# MCU.net
KiCad netlist of a schematic drawn in Altium Designer
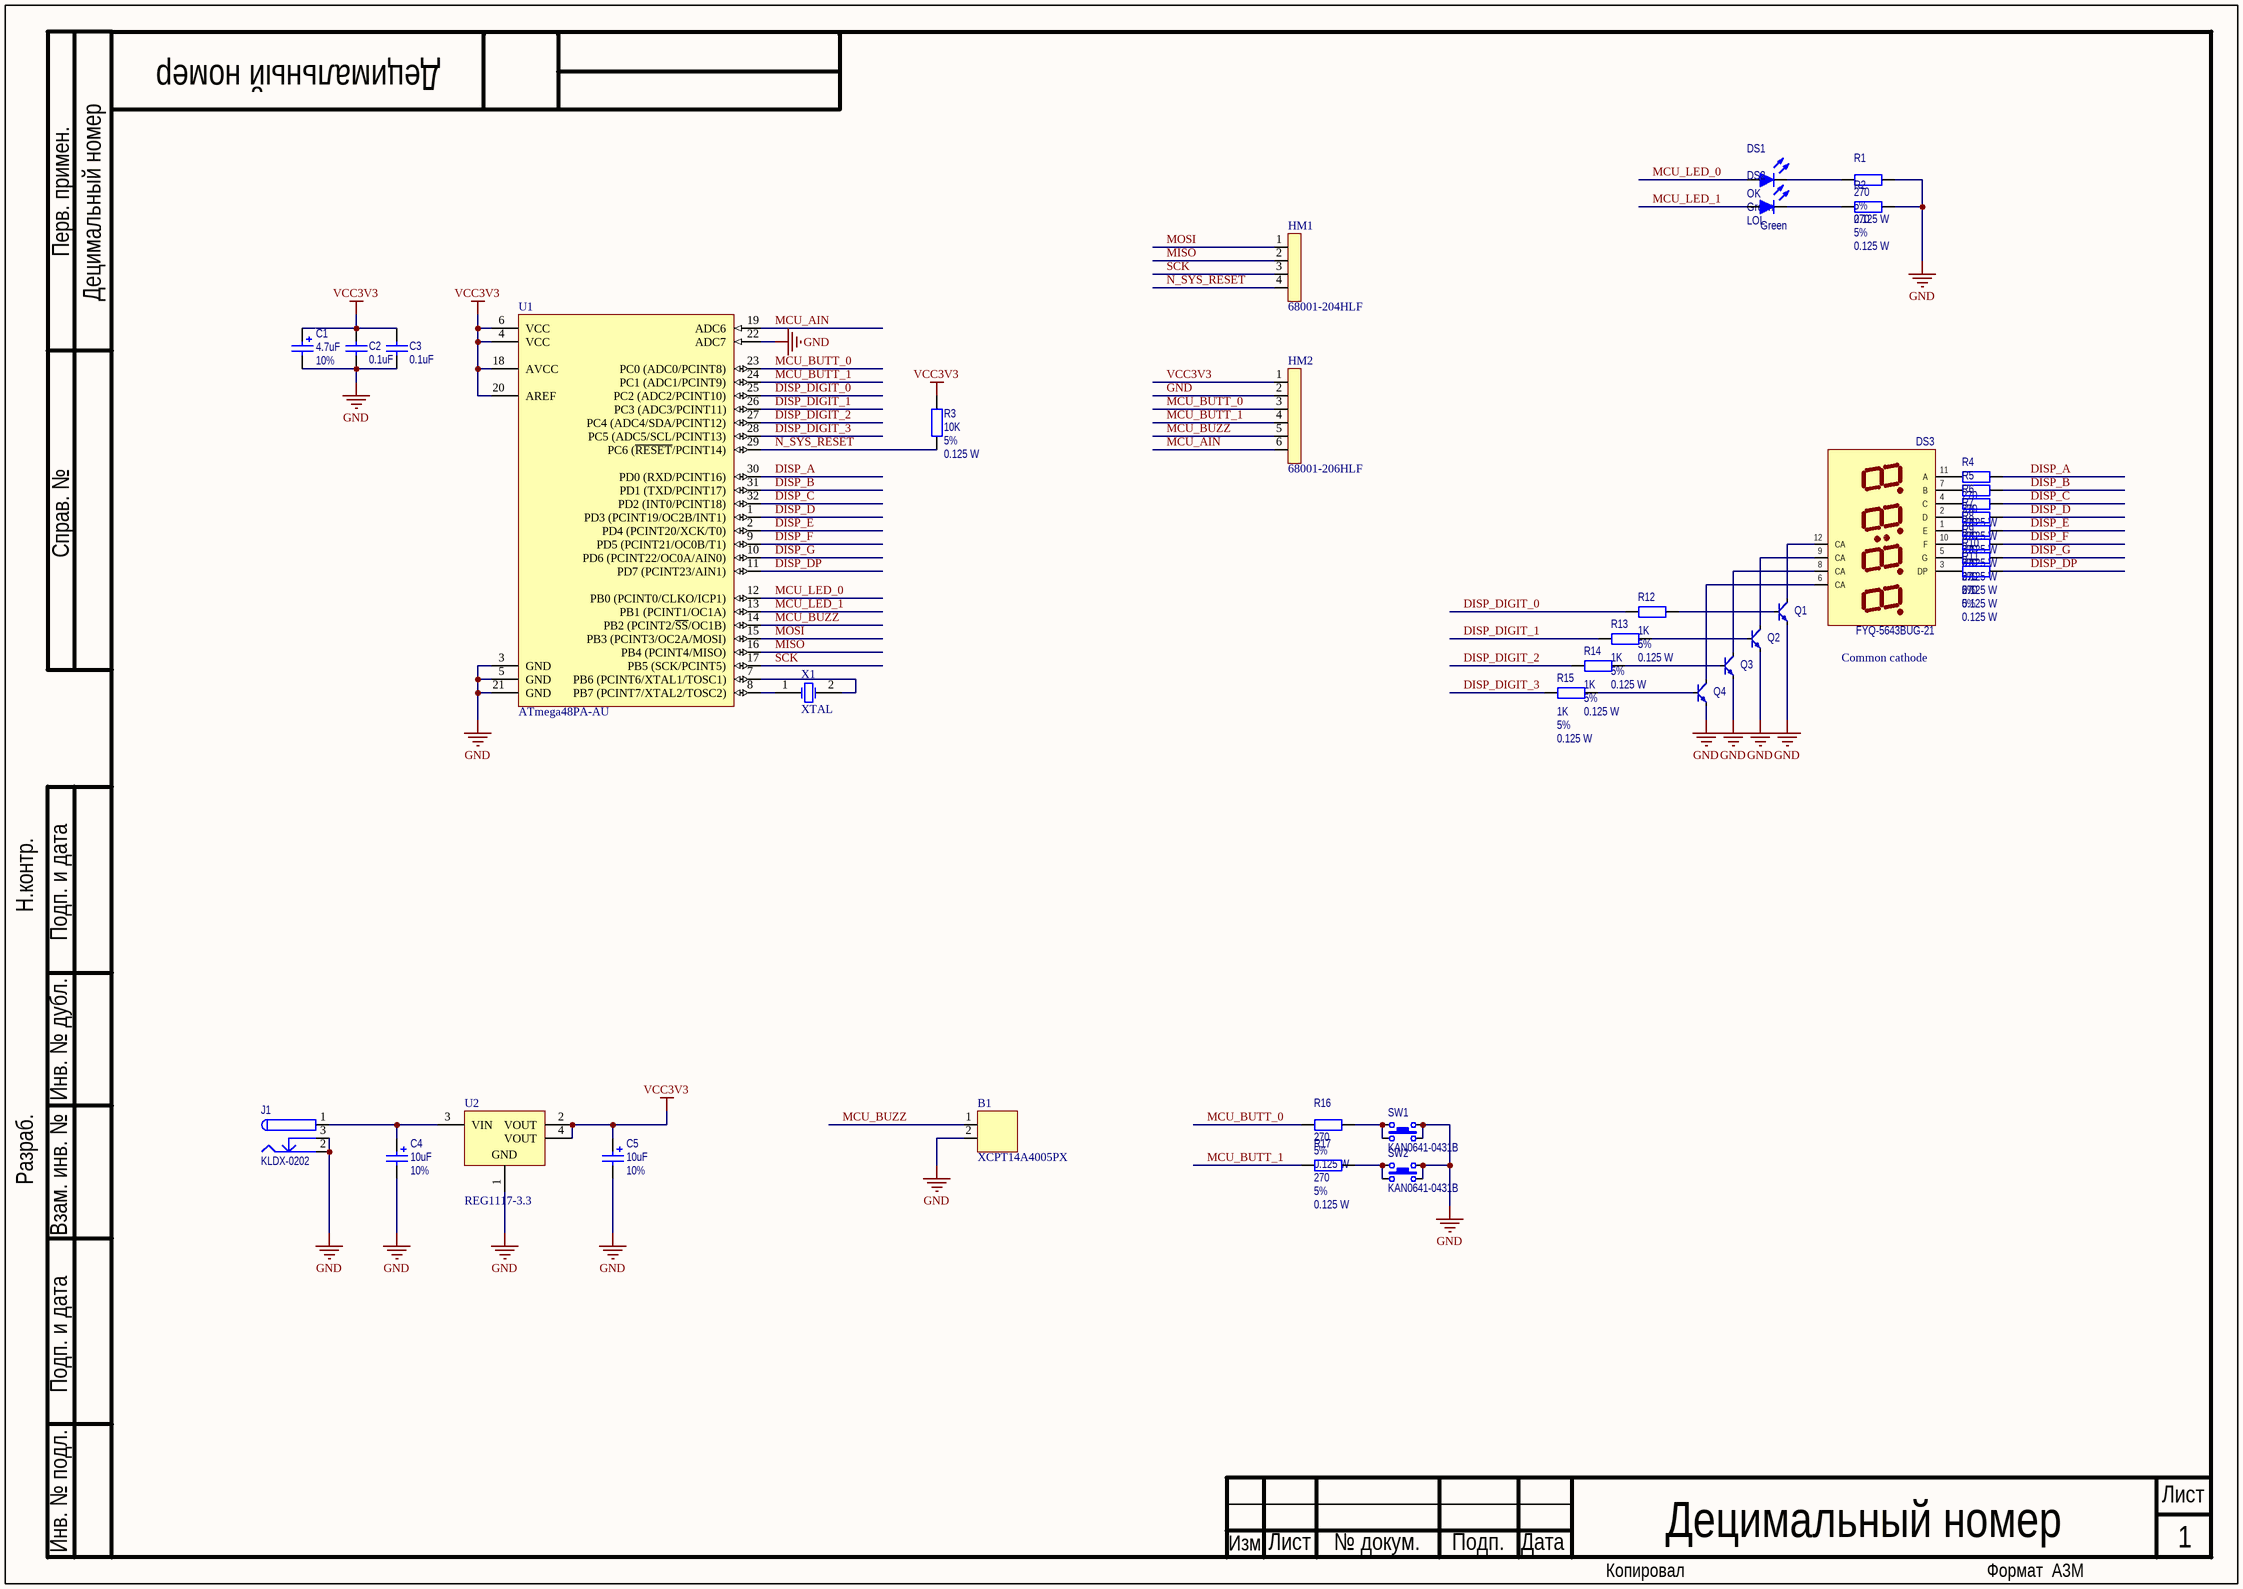
[diagram p0: MCU.SchDoc]

(export (version "E")
  (design (tool "Eeschema 10.0.6"))
  (components
    (comp (ref "B1")
      (value "XCPT14A4005PX")
      (footprint "ConstLibrary:XCPT14A4005PX")
      (description "Piezoelectric ceramic buzzer")
      (libsource (lib "ConstLibrary") (part "XCPT14A4005PX"))
    )
    (comp (ref "C1")
      (value "4.7uF")
      (footprint "ConstChipRCL:KEMET_A")
      (description "A size, STANDARD Tantalum Surface Mount Capacitors")
      (fields (field (name "TOLERANCE") "10%"))
      (libsource (lib "ConstChipRCL") (part "T491A***K***AH"))
    )
    (comp (ref "C2")
      (value "0.1uF")
      (footprint "ConstChipRCL:CAPC2012N")
      (description "0805 size MULTILAYER CERAMIC CHIP CAPACITOR, General (Up to 50V)")
      (libsource (lib "ConstChipRCL") (part "CGA4**X7R***********"))
    )
    (comp (ref "C3")
      (value "0.1uF")
      (footprint "ConstChipRCL:CAPC2012N")
      (description "0805 size MULTILAYER CERAMIC CHIP CAPACITOR, General (Up to 50V)")
      (libsource (lib "ConstChipRCL") (part "CGA4**X7R***********"))
    )
    (comp (ref "C4")
      (value "10uF")
      (footprint "ConstChipRCL:KEMET_A")
      (description "A size, STANDARD Tantalum Surface Mount Capacitors")
      (fields (field (name "TOLERANCE") "10%"))
      (libsource (lib "ConstChipRCL") (part "T491A***K***AH"))
    )
    (comp (ref "C5")
      (value "10uF")
      (footprint "ConstChipRCL:KEMET_A")
      (description "A size, STANDARD Tantalum Surface Mount Capacitors")
      (fields (field (name "TOLERANCE") "10%"))
      (libsource (lib "ConstChipRCL") (part "T491A***K***AH"))
    )
    (comp (ref "DS1")
      (value "OK")
      (footprint "ConstChipRCL:LED_1206")
      (description "Green LED, STANDARD BRIGHT 1206")
      (fields
        (field (name "MANUFACTURER") "Everlight Electronics Co Ltd")
        (field (name "ALTIUM_VALUE") "Green")
      )
      (libsource (lib "ConstChipRCL") (part "QTLP650C4TR"))
    )
    (comp (ref "DS2")
      (value "LOL")
      (footprint "ConstChipRCL:LED_1206")
      (description "Green LED, STANDARD BRIGHT 1206")
      (fields
        (field (name "MANUFACTURER") "Everlight Electronics Co Ltd")
        (field (name "ALTIUM_VALUE") "Green")
      )
      (libsource (lib "ConstChipRCL") (part "QTLP650C4TR"))
    )
    (comp (ref "DS3")
      (value "FYQ-5643BUG-21")
      (footprint "ConstLibrary:FYQ-5643BUG-21")
      (description "Segment indicator")
      (libsource (lib "ConstLibrary") (part "FYQ-5643BUG-21"))
    )
    (comp (ref "HM1")
      (value "68001-204HLF")
      (footprint "ConstLibrary:HEADER-1X4")
      (description "1x4 PIN HEADER .100\" SR STRAIGHT")
      (libsource (lib "ConstLibrary") (part "68001-204HLF"))
    )
    (comp (ref "HM2")
      (value "68001-206HLF")
      (footprint "ConstLibrary:HEADER-1X6")
      (description "1x6 PIN HEADER .100\" SR STRAIGHT")
      (libsource (lib "ConstLibrary") (part "68001-206HLF"))
    )
    (comp (ref "J1")
      (value "KLDX-0202")
      (footprint "ConstLibrary:KLDX-0202")
      (description "Low Voltage Power Supply Connector")
      (libsource (lib "ConstLibrary") (part "KLDX-0202"))
    )
    (comp (ref "Q1")
      (value "BC817")
      (footprint "ConstLibrary:SOT23-3L")
      (description "45 V, 500 mA NPN general-purpose transistors")
      (libsource (lib "ConstLibrary") (part "BC817"))
    )
    (comp (ref "Q2")
      (value "BC817")
      (footprint "ConstLibrary:SOT23-3L")
      (description "45 V, 500 mA NPN general-purpose transistors")
      (libsource (lib "ConstLibrary") (part "BC817"))
    )
    (comp (ref "Q3")
      (value "BC817")
      (footprint "ConstLibrary:SOT23-3L")
      (description "45 V, 500 mA NPN general-purpose transistors")
      (libsource (lib "ConstLibrary") (part "BC817"))
    )
    (comp (ref "Q4")
      (value "BC817")
      (footprint "ConstLibrary:SOT23-3L")
      (description "45 V, 500 mA NPN general-purpose transistors")
      (libsource (lib "ConstLibrary") (part "BC817"))
    )
    (comp (ref "R1")
      (value "270")
      (footprint "ConstChipRCL:RESC2012N")
      (description "0805 size, STANDARD thick Film Chip Resistor")
      (fields
        (field (name "MANUFACTURER") "Panasonic")
        (field (name "TOLERANCE") "5%")
        (field (name "POWER RATING") "0.125 W")
      )
      (libsource (lib "ConstChipRCL") (part "ERJ6GEYJ***V"))
    )
    (comp (ref "R2")
      (value "270")
      (footprint "ConstChipRCL:RESC2012N")
      (description "0805 size, STANDARD thick Film Chip Resistor")
      (fields
        (field (name "MANUFACTURER") "Panasonic")
        (field (name "TOLERANCE") "5%")
        (field (name "POWER RATING") "0.125 W")
      )
      (libsource (lib "ConstChipRCL") (part "ERJ6GEYJ***V"))
    )
    (comp (ref "R3")
      (value "10K")
      (footprint "ConstChipRCL:RESC2012N")
      (description "0805 size, STANDARD thick Film Chip Resistor")
      (fields
        (field (name "MANUFACTURER") "Panasonic")
        (field (name "TOLERANCE") "5%")
        (field (name "POWER RATING") "0.125 W")
      )
      (libsource (lib "") (part "ERJ6GEYJ***V_1"))
    )
    (comp (ref "R4")
      (value "270")
      (footprint "ConstChipRCL:RESC2012N")
      (description "0805 size, STANDARD thick Film Chip Resistor")
      (fields
        (field (name "MANUFACTURER") "Panasonic")
        (field (name "TOLERANCE") "5%")
        (field (name "POWER RATING") "0.125 W")
      )
      (libsource (lib "ConstChipRCL") (part "ERJ6GEYJ***V"))
    )
    (comp (ref "R5")
      (value "270")
      (footprint "ConstChipRCL:RESC2012N")
      (description "0805 size, STANDARD thick Film Chip Resistor")
      (fields
        (field (name "MANUFACTURER") "Panasonic")
        (field (name "TOLERANCE") "5%")
        (field (name "POWER RATING") "0.125 W")
      )
      (libsource (lib "ConstChipRCL") (part "ERJ6GEYJ***V"))
    )
    (comp (ref "R6")
      (value "270")
      (footprint "ConstChipRCL:RESC2012N")
      (description "0805 size, STANDARD thick Film Chip Resistor")
      (fields
        (field (name "MANUFACTURER") "Panasonic")
        (field (name "TOLERANCE") "5%")
        (field (name "POWER RATING") "0.125 W")
      )
      (libsource (lib "ConstChipRCL") (part "ERJ6GEYJ***V"))
    )
    (comp (ref "R7")
      (value "270")
      (footprint "ConstChipRCL:RESC2012N")
      (description "0805 size, STANDARD thick Film Chip Resistor")
      (fields
        (field (name "MANUFACTURER") "Panasonic")
        (field (name "TOLERANCE") "5%")
        (field (name "POWER RATING") "0.125 W")
      )
      (libsource (lib "ConstChipRCL") (part "ERJ6GEYJ***V"))
    )
    (comp (ref "R8")
      (value "270")
      (footprint "ConstChipRCL:RESC2012N")
      (description "0805 size, STANDARD thick Film Chip Resistor")
      (fields
        (field (name "MANUFACTURER") "Panasonic")
        (field (name "TOLERANCE") "5%")
        (field (name "POWER RATING") "0.125 W")
      )
      (libsource (lib "ConstChipRCL") (part "ERJ6GEYJ***V"))
    )
    (comp (ref "R9")
      (value "270")
      (footprint "ConstChipRCL:RESC2012N")
      (description "0805 size, STANDARD thick Film Chip Resistor")
      (fields
        (field (name "MANUFACTURER") "Panasonic")
        (field (name "TOLERANCE") "5%")
        (field (name "POWER RATING") "0.125 W")
      )
      (libsource (lib "ConstChipRCL") (part "ERJ6GEYJ***V"))
    )
    (comp (ref "R10")
      (value "270")
      (footprint "ConstChipRCL:RESC2012N")
      (description "0805 size, STANDARD thick Film Chip Resistor")
      (fields
        (field (name "MANUFACTURER") "Panasonic")
        (field (name "TOLERANCE") "5%")
        (field (name "POWER RATING") "0.125 W")
      )
      (libsource (lib "ConstChipRCL") (part "ERJ6GEYJ***V"))
    )
    (comp (ref "R11")
      (value "270")
      (footprint "ConstChipRCL:RESC2012N")
      (description "0805 size, STANDARD thick Film Chip Resistor")
      (fields
        (field (name "MANUFACTURER") "Panasonic")
        (field (name "TOLERANCE") "5%")
        (field (name "POWER RATING") "0.125 W")
      )
      (libsource (lib "ConstChipRCL") (part "ERJ6GEYJ***V"))
    )
    (comp (ref "R12")
      (value "1K")
      (footprint "ConstChipRCL:RESC2012N")
      (description "0805 size, STANDARD thick Film Chip Resistor")
      (fields
        (field (name "MANUFACTURER") "Panasonic")
        (field (name "TOLERANCE") "5%")
        (field (name "POWER RATING") "0.125 W")
      )
      (libsource (lib "ConstChipRCL") (part "ERJ6GEYJ***V"))
    )
    (comp (ref "R13")
      (value "1K")
      (footprint "ConstChipRCL:RESC2012N")
      (description "0805 size, STANDARD thick Film Chip Resistor")
      (fields
        (field (name "MANUFACTURER") "Panasonic")
        (field (name "TOLERANCE") "5%")
        (field (name "POWER RATING") "0.125 W")
      )
      (libsource (lib "ConstChipRCL") (part "ERJ6GEYJ***V"))
    )
    (comp (ref "R14")
      (value "1K")
      (footprint "ConstChipRCL:RESC2012N")
      (description "0805 size, STANDARD thick Film Chip Resistor")
      (fields
        (field (name "MANUFACTURER") "Panasonic")
        (field (name "TOLERANCE") "5%")
        (field (name "POWER RATING") "0.125 W")
      )
      (libsource (lib "ConstChipRCL") (part "ERJ6GEYJ***V"))
    )
    (comp (ref "R15")
      (value "1K")
      (footprint "ConstChipRCL:RESC2012N")
      (description "0805 size, STANDARD thick Film Chip Resistor")
      (fields
        (field (name "MANUFACTURER") "Panasonic")
        (field (name "TOLERANCE") "5%")
        (field (name "POWER RATING") "0.125 W")
      )
      (libsource (lib "ConstChipRCL") (part "ERJ6GEYJ***V"))
    )
    (comp (ref "R16")
      (value "270")
      (footprint "ConstChipRCL:RESC2012N")
      (description "0805 size, STANDARD thick Film Chip Resistor")
      (fields
        (field (name "MANUFACTURER") "Panasonic")
        (field (name "TOLERANCE") "5%")
        (field (name "POWER RATING") "0.125 W")
      )
      (libsource (lib "ConstChipRCL") (part "ERJ6GEYJ***V"))
    )
    (comp (ref "R17")
      (value "270")
      (footprint "ConstChipRCL:RESC2012N")
      (description "0805 size, STANDARD thick Film Chip Resistor")
      (fields
        (field (name "MANUFACTURER") "Panasonic")
        (field (name "TOLERANCE") "5%")
        (field (name "POWER RATING") "0.125 W")
      )
      (libsource (lib "ConstChipRCL") (part "ERJ6GEYJ***V"))
    )
    (comp (ref "SW1")
      (value "KAN0641-0431B")
      (footprint "ConstLibrary:KAN0641")
      (description "Tact switch, button SMD")
      (libsource (lib "ConstLibrary") (part "KAN0641-0431B"))
    )
    (comp (ref "SW2")
      (value "KAN0641-0431B")
      (footprint "ConstLibrary:KAN0641")
      (description "Tact switch, button SMD")
      (libsource (lib "ConstLibrary") (part "KAN0641-0431B"))
    )
    (comp (ref "U1")
      (value "ATmega48PA-AU")
      (footprint "32A_N")
      (fields (field (name "PUBLISHER") "Altium Limited"))
      (libsource (lib "Atmel Microcontroller 8-Bit megaAVR") (part "ATmega48PA-AU"))
    )
    (comp (ref "U2")
      (value "REG1117-3.3")
      (footprint "TI-DCY4_N")
      (libsource (lib "TI Power Management Linear Regulator Single Channel LDO (400-7500mA)") (part "REG1117-3.3"))
    )
    (comp (ref "X1")
      (value "XTAL")
      (footprint "R38")
      (description "Crystal Oscillator")
      (fields (field (name "PUBLISHER") "Altium Limited"))
      (libsource (lib "Miscellaneous Devices") (part "XTAL"))
    )
  )
  (nets
    (net (code "1") (name "/DISP_A") (class "Default")
      (node (ref "R4") (pin "2") (pinfunction "2_2") (pintype "passive"))
      (node (ref "U1") (pin "30") (pinfunction "PD0_(RXD/PCINT16)_30") (pintype "bidirectional"))
    )
    (net (code "2") (name "/DISP_B") (class "Default")
      (node (ref "R5") (pin "2") (pinfunction "2_2") (pintype "passive"))
      (node (ref "U1") (pin "31") (pinfunction "PD1_(TXD/PCINT17)_31") (pintype "bidirectional"))
    )
    (net (code "3") (name "/DISP_C") (class "Default")
      (node (ref "R6") (pin "2") (pinfunction "2_2") (pintype "passive"))
      (node (ref "U1") (pin "32") (pinfunction "PD2_(INT0/PCINT18)_32") (pintype "bidirectional"))
    )
    (net (code "4") (name "/DISP_D") (class "Default")
      (node (ref "R7") (pin "2") (pinfunction "2_2") (pintype "passive"))
      (node (ref "U1") (pin "1") (pinfunction "PD3_(PCINT19/OC2B/INT1)_1") (pintype "bidirectional"))
    )
    (net (code "5") (name "/DISP_DIGIT_0") (class "Default")
      (node (ref "R12") (pin "1") (pinfunction "1_1") (pintype "passive"))
      (node (ref "U1") (pin "25") (pinfunction "PC2_(ADC2/PCINT10)_25") (pintype "bidirectional"))
    )
    (net (code "6") (name "/DISP_DIGIT_1") (class "Default")
      (node (ref "R13") (pin "1") (pinfunction "1_1") (pintype "passive"))
      (node (ref "U1") (pin "26") (pinfunction "PC3_(ADC3/PCINT11)_26") (pintype "bidirectional"))
    )
    (net (code "7") (name "/DISP_DIGIT_2") (class "Default")
      (node (ref "R14") (pin "1") (pinfunction "1_1") (pintype "passive"))
      (node (ref "U1") (pin "27") (pinfunction "PC4_(ADC4/SDA/PCINT12)_27") (pintype "bidirectional"))
    )
    (net (code "8") (name "/DISP_DIGIT_3") (class "Default")
      (node (ref "R15") (pin "1") (pinfunction "1_1") (pintype "passive"))
      (node (ref "U1") (pin "28") (pinfunction "PC5_(ADC5/SCL/PCINT13)_28") (pintype "bidirectional"))
    )
    (net (code "9") (name "/DISP_DP") (class "Default")
      (node (ref "R11") (pin "2") (pinfunction "2_2") (pintype "passive"))
      (node (ref "U1") (pin "11") (pinfunction "PD7_(PCINT23/AIN1)_11") (pintype "bidirectional"))
    )
    (net (code "10") (name "/DISP_E") (class "Default")
      (node (ref "R8") (pin "2") (pinfunction "2_2") (pintype "passive"))
      (node (ref "U1") (pin "2") (pinfunction "PD4_(PCINT20/XCK/T0)_2") (pintype "bidirectional"))
    )
    (net (code "11") (name "/DISP_F") (class "Default")
      (node (ref "R9") (pin "2") (pinfunction "2_2") (pintype "passive"))
      (node (ref "U1") (pin "9") (pinfunction "PD5_(PCINT21/OC0B/T1)_9") (pintype "bidirectional"))
    )
    (net (code "12") (name "/DISP_G") (class "Default")
      (node (ref "R10") (pin "2") (pinfunction "2_2") (pintype "passive"))
      (node (ref "U1") (pin "10") (pinfunction "PD6_(PCINT22/OC0A/AIN0)_10") (pintype "bidirectional"))
    )
    (net (code "13") (name "/MCU_AIN") (class "Default")
      (node (ref "HM2") (pin "6") (pinfunction "6_6") (pintype "passive"))
      (node (ref "U1") (pin "19") (pinfunction "ADC6_19") (pintype "input"))
    )
    (net (code "14") (name "/MCU_BUTT_0") (class "Default")
      (node (ref "HM2") (pin "3") (pinfunction "3_3") (pintype "passive"))
      (node (ref "R16") (pin "1") (pinfunction "1_1") (pintype "passive"))
      (node (ref "U1") (pin "23") (pinfunction "PC0_(ADC0/PCINT8)_23") (pintype "bidirectional"))
    )
    (net (code "15") (name "/MCU_BUTT_1") (class "Default")
      (node (ref "HM2") (pin "4") (pinfunction "4_4") (pintype "passive"))
      (node (ref "R17") (pin "1") (pinfunction "1_1") (pintype "passive"))
      (node (ref "U1") (pin "24") (pinfunction "PC1_(ADC1/PCINT9)_24") (pintype "bidirectional"))
    )
    (net (code "16") (name "/MCU_BUZZ") (class "Default")
      (node (ref "B1") (pin "1") (pinfunction "1_1") (pintype "passive"))
      (node (ref "HM2") (pin "5") (pinfunction "5_5") (pintype "passive"))
      (node (ref "U1") (pin "14") (pinfunction "PB2_(PCINT2/~{SS}/OC1B)_14") (pintype "bidirectional"))
    )
    (net (code "17") (name "/MCU_LED_0") (class "Default")
      (node (ref "DS1") (pin "1") (pinfunction "A_1") (pintype "passive"))
      (node (ref "U1") (pin "12") (pinfunction "PB0_(PCINT0/CLKO/ICP1)_12") (pintype "bidirectional"))
    )
    (net (code "18") (name "/MCU_LED_1") (class "Default")
      (node (ref "DS2") (pin "1") (pinfunction "A_1") (pintype "passive"))
      (node (ref "U1") (pin "13") (pinfunction "PB1_(PCINT1/OC1A)_13") (pintype "bidirectional"))
    )
    (net (code "19") (name "/MISO") (class "Default")
      (node (ref "HM1") (pin "2") (pinfunction "2_2") (pintype "passive"))
      (node (ref "U1") (pin "16") (pinfunction "PB4_(PCINT4/MISO)_16") (pintype "bidirectional"))
    )
    (net (code "20") (name "/MOSI") (class "Default")
      (node (ref "HM1") (pin "1") (pinfunction "1_1") (pintype "passive"))
      (node (ref "U1") (pin "15") (pinfunction "PB3_(PCINT3/OC2A/MOSI)_15") (pintype "bidirectional"))
    )
    (net (code "21") (name "/N_SYS_RESET") (class "Default")
      (node (ref "HM1") (pin "4") (pinfunction "4_4") (pintype "passive"))
      (node (ref "R3") (pin "2") (pinfunction "2_2") (pintype "passive"))
      (node (ref "U1") (pin "29") (pinfunction "PC6_(~{RESET}/PCINT14)_29") (pintype "bidirectional"))
    )
    (net (code "22") (name "/SCK") (class "Default")
      (node (ref "HM1") (pin "3") (pinfunction "3_3") (pintype "passive"))
      (node (ref "U1") (pin "17") (pinfunction "PB5_(SCK/PCINT5)_17") (pintype "bidirectional"))
    )
    (net (code "23") (name "GND") (class "Default")
      (node (ref "B1") (pin "2") (pinfunction "2_2") (pintype "passive"))
      (node (ref "C1") (pin "2") (pinfunction "2_2") (pintype "passive"))
      (node (ref "C2") (pin "1") (pinfunction "1_1") (pintype "passive"))
      (node (ref "C3") (pin "1") (pinfunction "1_1") (pintype "passive"))
      (node (ref "C4") (pin "2") (pinfunction "2_2") (pintype "passive"))
      (node (ref "C5") (pin "2") (pinfunction "2_2") (pintype "passive"))
      (node (ref "HM2") (pin "2") (pinfunction "2_2") (pintype "passive"))
      (node (ref "J1") (pin "2") (pinfunction "2_2") (pintype "power_in"))
      (node (ref "J1") (pin "3") (pinfunction "3_3") (pintype "power_in"))
      (node (ref "Q1") (pin "2") (pinfunction "2_2") (pintype "passive"))
      (node (ref "Q2") (pin "2") (pinfunction "2_2") (pintype "passive"))
      (node (ref "Q3") (pin "2") (pinfunction "2_2") (pintype "passive"))
      (node (ref "Q4") (pin "2") (pinfunction "2_2") (pintype "passive"))
      (node (ref "R1") (pin "2") (pinfunction "2_2") (pintype "passive"))
      (node (ref "R2") (pin "2") (pinfunction "2_2") (pintype "passive"))
      (node (ref "SW1") (pin "3") (pinfunction "3_3") (pintype "passive"))
      (node (ref "SW1") (pin "4") (pinfunction "4_4") (pintype "passive"))
      (node (ref "SW2") (pin "3") (pinfunction "3_3") (pintype "passive"))
      (node (ref "SW2") (pin "4") (pinfunction "4_4") (pintype "passive"))
      (node (ref "U1") (pin "21") (pinfunction "GND_21") (pintype "power_in"))
      (node (ref "U1") (pin "22") (pinfunction "ADC7_22") (pintype "input"))
      (node (ref "U1") (pin "3") (pinfunction "GND_3") (pintype "power_in"))
      (node (ref "U1") (pin "5") (pinfunction "GND_5") (pintype "power_in"))
      (node (ref "U2") (pin "1") (pinfunction "GND_1") (pintype "power_in"))
    )
    (net (code "24") (name "Net-(DS1-K)") (class "Default")
      (node (ref "DS1") (pin "2") (pinfunction "K_2") (pintype "passive"))
      (node (ref "R1") (pin "1") (pinfunction "1_1") (pintype "passive"))
    )
    (net (code "25") (name "Net-(DS2-K)") (class "Default")
      (node (ref "DS2") (pin "2") (pinfunction "K_2") (pintype "passive"))
      (node (ref "R2") (pin "1") (pinfunction "1_1") (pintype "passive"))
    )
    (net (code "26") (name "Net-(DS3-A)") (class "Default")
      (node (ref "DS3") (pin "11") (pinfunction "A_11") (pintype "passive"))
      (node (ref "R4") (pin "1") (pinfunction "1_1") (pintype "passive"))
    )
    (net (code "27") (name "Net-(DS3-B)") (class "Default")
      (node (ref "DS3") (pin "7") (pinfunction "B_7") (pintype "passive"))
      (node (ref "R5") (pin "1") (pinfunction "1_1") (pintype "passive"))
    )
    (net (code "28") (name "Net-(DS3-C)") (class "Default")
      (node (ref "DS3") (pin "4") (pinfunction "C_4") (pintype "passive"))
      (node (ref "R6") (pin "1") (pinfunction "1_1") (pintype "passive"))
    )
    (net (code "29") (name "Net-(DS3-CA-Pad6)") (class "Default")
      (node (ref "DS3") (pin "6") (pinfunction "CA_6") (pintype "passive"))
      (node (ref "Q4") (pin "3") (pinfunction "3_3") (pintype "passive"))
    )
    (net (code "30") (name "Net-(DS3-CA-Pad8)") (class "Default")
      (node (ref "DS3") (pin "8") (pinfunction "CA_8") (pintype "passive"))
      (node (ref "Q3") (pin "3") (pinfunction "3_3") (pintype "passive"))
    )
    (net (code "31") (name "Net-(DS3-CA-Pad9)") (class "Default")
      (node (ref "DS3") (pin "9") (pinfunction "CA_9") (pintype "passive"))
      (node (ref "Q2") (pin "3") (pinfunction "3_3") (pintype "passive"))
    )
    (net (code "32") (name "Net-(DS3-CA-Pad12)") (class "Default")
      (node (ref "DS3") (pin "12") (pinfunction "CA_12") (pintype "passive"))
      (node (ref "Q1") (pin "3") (pinfunction "3_3") (pintype "passive"))
    )
    (net (code "33") (name "Net-(DS3-D)") (class "Default")
      (node (ref "DS3") (pin "2") (pinfunction "D_2") (pintype "passive"))
      (node (ref "R7") (pin "1") (pinfunction "1_1") (pintype "passive"))
    )
    (net (code "34") (name "Net-(DS3-DP)") (class "Default")
      (node (ref "DS3") (pin "3") (pinfunction "DP_3") (pintype "passive"))
      (node (ref "R11") (pin "1") (pinfunction "1_1") (pintype "passive"))
    )
    (net (code "35") (name "Net-(DS3-E)") (class "Default")
      (node (ref "DS3") (pin "1") (pinfunction "E_1") (pintype "passive"))
      (node (ref "R8") (pin "1") (pinfunction "1_1") (pintype "passive"))
    )
    (net (code "36") (name "Net-(DS3-F)") (class "Default")
      (node (ref "DS3") (pin "10") (pinfunction "F_10") (pintype "passive"))
      (node (ref "R9") (pin "1") (pinfunction "1_1") (pintype "passive"))
    )
    (net (code "37") (name "Net-(DS3-G)") (class "Default")
      (node (ref "DS3") (pin "5") (pinfunction "G_5") (pintype "passive"))
      (node (ref "R10") (pin "1") (pinfunction "1_1") (pintype "passive"))
    )
    (net (code "38") (name "Net-(Q1-Pad1)") (class "Default")
      (node (ref "Q1") (pin "1") (pinfunction "1_1") (pintype "passive"))
      (node (ref "R12") (pin "2") (pinfunction "2_2") (pintype "passive"))
    )
    (net (code "39") (name "Net-(Q2-Pad1)") (class "Default")
      (node (ref "Q2") (pin "1") (pinfunction "1_1") (pintype "passive"))
      (node (ref "R13") (pin "2") (pinfunction "2_2") (pintype "passive"))
    )
    (net (code "40") (name "Net-(Q3-Pad1)") (class "Default")
      (node (ref "Q3") (pin "1") (pinfunction "1_1") (pintype "passive"))
      (node (ref "R14") (pin "2") (pinfunction "2_2") (pintype "passive"))
    )
    (net (code "41") (name "Net-(Q4-Pad1)") (class "Default")
      (node (ref "Q4") (pin "1") (pinfunction "1_1") (pintype "passive"))
      (node (ref "R15") (pin "2") (pinfunction "2_2") (pintype "passive"))
    )
    (net (code "42") (name "Net-(R16-Pad2)") (class "Default")
      (node (ref "R16") (pin "2") (pinfunction "2_2") (pintype "passive"))
      (node (ref "SW1") (pin "1") (pinfunction "1_1") (pintype "passive"))
      (node (ref "SW1") (pin "2") (pinfunction "2_2") (pintype "passive"))
    )
    (net (code "43") (name "Net-(R17-Pad2)") (class "Default")
      (node (ref "R17") (pin "2") (pinfunction "2_2") (pintype "passive"))
      (node (ref "SW2") (pin "1") (pinfunction "1_1") (pintype "passive"))
      (node (ref "SW2") (pin "2") (pinfunction "2_2") (pintype "passive"))
    )
    (net (code "44") (name "Net-(U1-PB6_(PCINT6{slash}XTAL1{slash}TOSC1))") (class "Default")
      (node (ref "U1") (pin "7") (pinfunction "PB6_(PCINT6/XTAL1/TOSC1)_7") (pintype "bidirectional"))
      (node (ref "X1") (pin "2") (pinfunction "OSC2_2") (pintype "passive"))
    )
    (net (code "45") (name "Net-(U1-PB7_(PCINT7{slash}XTAL2{slash}TOSC2))") (class "Default")
      (node (ref "U1") (pin "8") (pinfunction "PB7_(PCINT7/XTAL2/TOSC2)_8") (pintype "bidirectional"))
      (node (ref "X1") (pin "1") (pinfunction "OSC1_1") (pintype "passive"))
    )
    (net (code "46") (name "Net-(U2-VIN)") (class "Default")
      (node (ref "C4") (pin "1") (pinfunction "1_1") (pintype "passive"))
      (node (ref "J1") (pin "1") (pinfunction "1_1") (pintype "power_in"))
      (node (ref "U2") (pin "3") (pinfunction "VIN_3") (pintype "power_in"))
    )
    (net (code "47") (name "VCC3V3") (class "Default")
      (node (ref "C1") (pin "1") (pinfunction "1_1") (pintype "passive"))
      (node (ref "C2") (pin "2") (pinfunction "2_2") (pintype "passive"))
      (node (ref "C3") (pin "2") (pinfunction "2_2") (pintype "passive"))
      (node (ref "C5") (pin "1") (pinfunction "1_1") (pintype "passive"))
      (node (ref "HM2") (pin "1") (pinfunction "1_1") (pintype "passive"))
      (node (ref "R3") (pin "1") (pinfunction "1_1") (pintype "passive"))
      (node (ref "U1") (pin "18") (pinfunction "AVCC_18") (pintype "power_in"))
      (node (ref "U1") (pin "20") (pinfunction "AREF_20") (pintype "passive"))
      (node (ref "U1") (pin "4") (pinfunction "VCC_4") (pintype "power_in"))
      (node (ref "U1") (pin "6") (pinfunction "VCC_6") (pintype "power_in"))
      (node (ref "U2") (pin "2") (pinfunction "VOUT_2") (pintype "power_in"))
      (node (ref "U2") (pin "4") (pinfunction "VOUT_4") (pintype "power_in"))
    )
  )
)
